# Drl_NEW.net
KiCad netlist of a schematic drawn in EAGLE
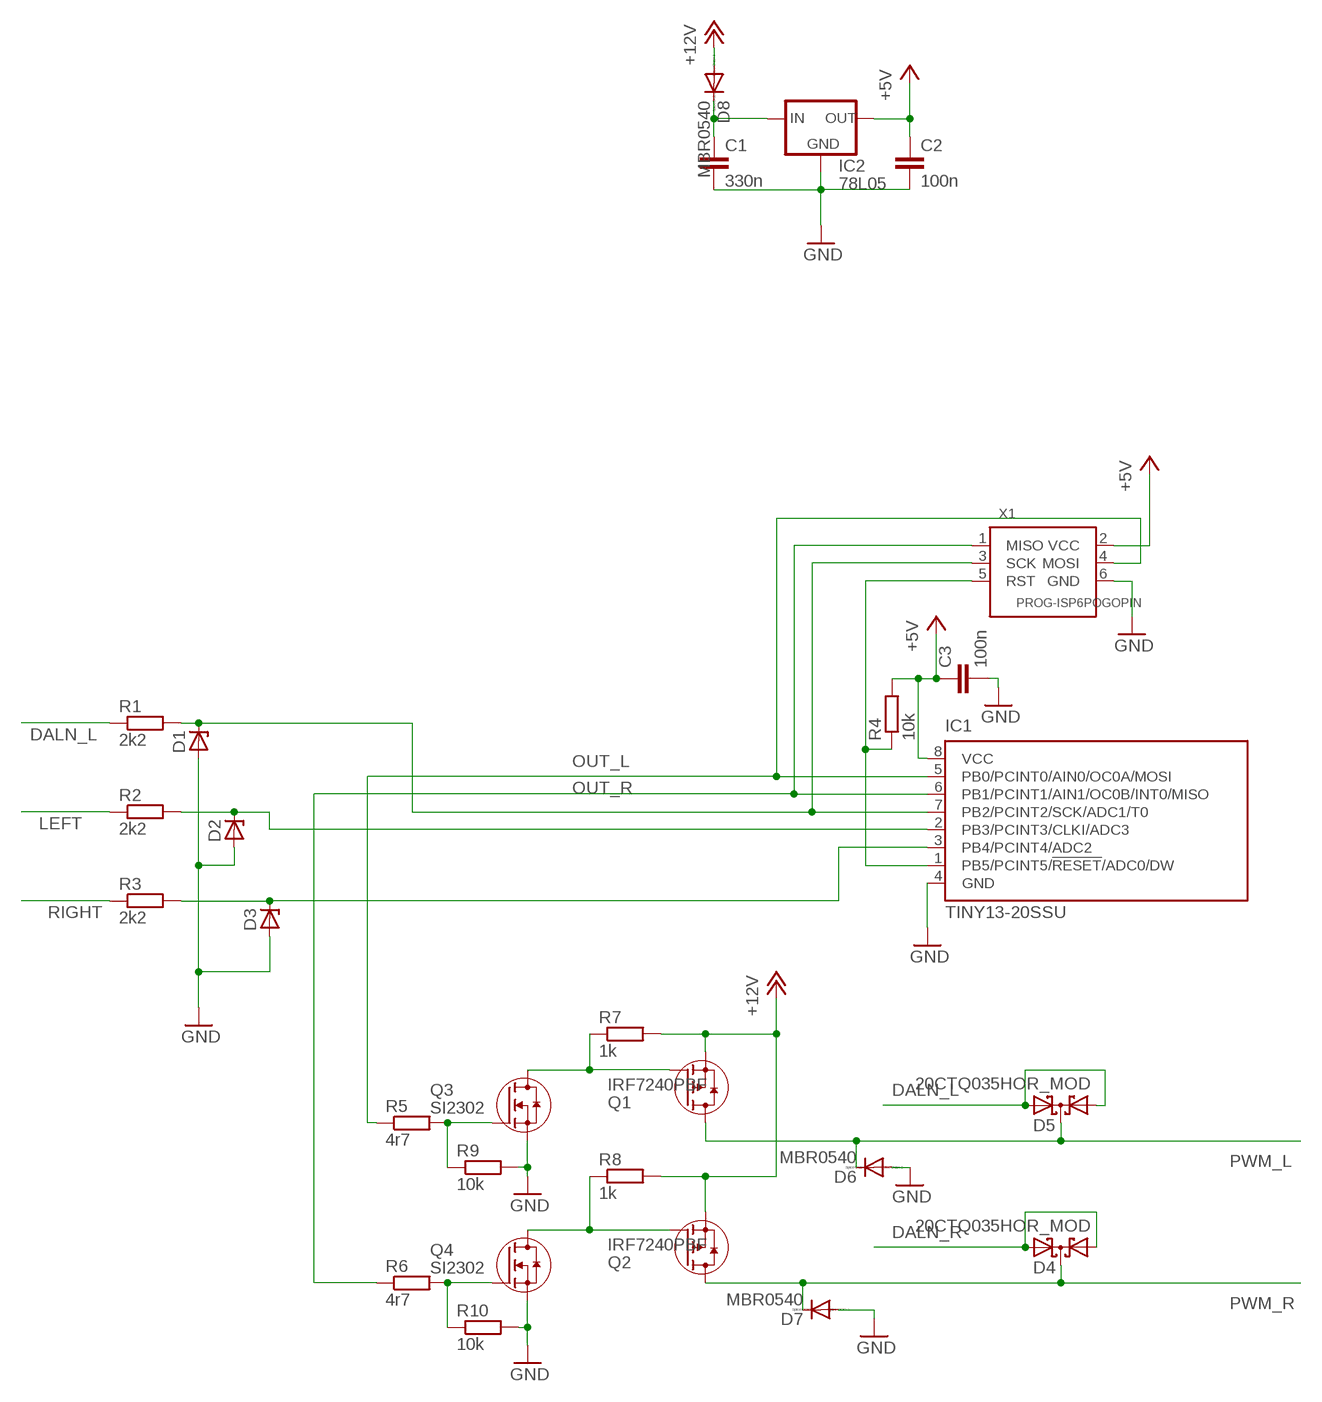
[diagram p0: schematic, sheet 1]

(export (version "E")
  (design (tool "Eeschema 10.0.6"))
  (components
    (comp (ref "C1")
      (value "330n")
      (footprint "eagle-import:C0805")
      (libsource (lib "eagle-import") (part "C-EUC0805"))
    )
    (comp (ref "C2")
      (value "100n")
      (footprint "eagle-import:C0805")
      (libsource (lib "eagle-import") (part "C-EUC0805"))
    )
    (comp (ref "C3")
      (value "100n")
      (footprint "eagle-import:C0805")
      (libsource (lib "eagle-import") (part "C-EUC0805"))
    )
    (comp (ref "D1")
      (value "ZENER-DIODESOD80C")
      (footprint "eagle-import:SOD80C")
      (libsource (lib "eagle-import") (part "ZENER-DIODESOD80C"))
    )
    (comp (ref "D2")
      (value "ZENER-DIODESOD80C")
      (footprint "eagle-import:SOD80C")
      (libsource (lib "eagle-import") (part "ZENER-DIODESOD80C"))
    )
    (comp (ref "D3")
      (value "ZENER-DIODESOD80C")
      (footprint "eagle-import:SOD80C")
      (libsource (lib "eagle-import") (part "ZENER-DIODESOD80C"))
    )
    (comp (ref "D4")
      (value "20CTQ035HOR_MOD")
      (footprint "eagle-import:TO220AB_MOD")
      (libsource (lib "eagle-import") (part "20CTQ035HOR_MOD"))
    )
    (comp (ref "D5")
      (value "20CTQ035HOR_MOD")
      (footprint "eagle-import:TO220AB_MOD")
      (libsource (lib "eagle-import") (part "20CTQ035HOR_MOD"))
    )
    (comp (ref "D6")
      (value "MBR0540")
      (footprint "eagle-import:SOD-123_MINI-SMA")
      (libsource (lib "eagle-import") (part "CGRM400-G1"))
    )
    (comp (ref "D7")
      (value "MBR0540")
      (footprint "eagle-import:SOD-123_MINI-SMA")
      (libsource (lib "eagle-import") (part "CGRM400-G1"))
    )
    (comp (ref "D8")
      (value "MBR0540")
      (footprint "eagle-import:SOD-123_MINI-SMA")
      (libsource (lib "eagle-import") (part "CGRM400-G1"))
    )
    (comp (ref "IC1")
      (value "TINY13-20SSU")
      (footprint "eagle-import:8S1")
      (fields (field (name "MPN") "ATTINY13-20SSU"))
      (libsource (lib "eagle-import") (part "TINY13SSU-20"))
    )
    (comp (ref "IC2")
      (value "78L05")
      (footprint "eagle-import:78LXX-SOT89")
      (libsource (lib "eagle-import") (part "78LXXSOT89"))
    )
    (comp (ref "Q1")
      (value "IRF7240PBF")
      (footprint "eagle-import:SO08")
      (libsource (lib "eagle-import") (part "IRF7240PBF"))
    )
    (comp (ref "Q2")
      (value "IRF7240PBF")
      (footprint "eagle-import:SO08")
      (libsource (lib "eagle-import") (part "IRF7240PBF"))
    )
    (comp (ref "Q3")
      (value "SI2302")
      (footprint "eagle-import:SOT-23-GSD")
      (libsource (lib "eagle-import") (part "SI2302"))
    )
    (comp (ref "Q4")
      (value "SI2302")
      (footprint "eagle-import:SOT-23-GSD")
      (libsource (lib "eagle-import") (part "SI2302"))
    )
    (comp (ref "R1")
      (value "2k2")
      (footprint "eagle-import:R0603")
      (libsource (lib "eagle-import") (part "R-EU_R0603"))
    )
    (comp (ref "R2")
      (value "2k2")
      (footprint "eagle-import:R0603")
      (libsource (lib "eagle-import") (part "R-EU_R0603"))
    )
    (comp (ref "R3")
      (value "2k2")
      (footprint "eagle-import:R0603")
      (libsource (lib "eagle-import") (part "R-EU_R0603"))
    )
    (comp (ref "R4")
      (value "10k")
      (footprint "eagle-import:R0603")
      (libsource (lib "eagle-import") (part "R-EU_R0603"))
    )
    (comp (ref "R5")
      (value "4r7")
      (footprint "eagle-import:R0603")
      (libsource (lib "eagle-import") (part "R-EU_R0603"))
    )
    (comp (ref "R6")
      (value "4r7")
      (footprint "eagle-import:R0603")
      (libsource (lib "eagle-import") (part "R-EU_R0603"))
    )
    (comp (ref "R7")
      (value "1k")
      (footprint "eagle-import:R0603")
      (libsource (lib "eagle-import") (part "R-EU_R0603"))
    )
    (comp (ref "R8")
      (value "1k")
      (footprint "eagle-import:R0603")
      (libsource (lib "eagle-import") (part "R-EU_R0603"))
    )
    (comp (ref "R9")
      (value "10k")
      (footprint "eagle-import:R0603")
      (libsource (lib "eagle-import") (part "R-EU_R0603"))
    )
    (comp (ref "R10")
      (value "10k")
      (footprint "eagle-import:R0603")
      (libsource (lib "eagle-import") (part "R-EU_R0603"))
    )
    (comp (ref "X1")
      (value "PROG-ISP6POGOPIN")
      (footprint "eagle-import:PROG_POGOPIN")
      (libsource (lib "eagle-import") (part "PROG-ISP6POGOPIN"))
    )
  )
  (nets
    (net (code "1") (name "+5V") (class "Default")
      (node (ref "C2") (pin "1") (pinfunction "1_1") (pintype "passive"))
      (node (ref "C3") (pin "1") (pinfunction "1_1") (pintype "passive"))
      (node (ref "IC1") (pin "8") (pinfunction "VCC_8") (pintype "power_in"))
      (node (ref "IC2") (pin "OUT") (pinfunction "OUT_OUT") (pintype "passive"))
      (node (ref "R4") (pin "2") (pinfunction "2_2") (pintype "passive"))
      (node (ref "X1") (pin "2") (pinfunction "VCC_2") (pintype "bidirectional"))
    )
    (net (code "2") (name "+12V") (class "Default")
      (node (ref "D8") (pin "A") (pinfunction "A_A") (pintype "passive"))
      (node (ref "Q1") (pin "1") (pinfunction "S_1") (pintype "passive"))
      (node (ref "Q1") (pin "2") (pinfunction "S_2") (pintype "passive"))
      (node (ref "Q1") (pin "3") (pinfunction "S_3") (pintype "passive"))
      (node (ref "Q2") (pin "1") (pinfunction "S_1") (pintype "passive"))
      (node (ref "Q2") (pin "2") (pinfunction "S_2") (pintype "passive"))
      (node (ref "Q2") (pin "3") (pinfunction "S_3") (pintype "passive"))
      (node (ref "R7") (pin "2") (pinfunction "2_2") (pintype "passive"))
      (node (ref "R8") (pin "2") (pinfunction "2_2") (pintype "passive"))
    )
    (net (code "3") (name "/DALN_L") (class "Default")
      (node (ref "D5") (pin "A1") (pinfunction "A1_A1") (pintype "passive"))
      (node (ref "D5") (pin "A2") (pinfunction "A2_A2") (pintype "passive"))
      (node (ref "R1") (pin "1") (pinfunction "1_1") (pintype "passive"))
    )
    (net (code "4") (name "/DALN_R") (class "Default")
      (node (ref "D4") (pin "A1") (pinfunction "A1_A1") (pintype "passive"))
      (node (ref "D4") (pin "A2") (pinfunction "A2_A2") (pintype "passive"))
    )
    (net (code "5") (name "/LEFT") (class "Default")
      (node (ref "R2") (pin "1") (pinfunction "1_1") (pintype "passive"))
    )
    (net (code "6") (name "/OUT_L") (class "Default")
      (node (ref "IC1") (pin "5") (pinfunction "PB0/PCINT0/AIN0/OC0A/MOSI_5") (pintype "bidirectional"))
      (node (ref "R5") (pin "1") (pinfunction "1_1") (pintype "passive"))
      (node (ref "X1") (pin "4") (pinfunction "MOSI_4") (pintype "bidirectional"))
    )
    (net (code "7") (name "/OUT_R") (class "Default")
      (node (ref "IC1") (pin "6") (pinfunction "PB1/PCINT1/AIN1/OC0B/INT0/MISO_6") (pintype "bidirectional"))
      (node (ref "R6") (pin "1") (pinfunction "1_1") (pintype "passive"))
      (node (ref "X1") (pin "1") (pinfunction "MISO_1") (pintype "bidirectional"))
    )
    (net (code "8") (name "/PWM_L") (class "Default")
      (node (ref "D5") (pin "C") (pinfunction "C_C") (pintype "passive"))
      (node (ref "D6") (pin "C") (pinfunction "C_C") (pintype "passive"))
      (node (ref "Q1") (pin "5") (pinfunction "D_5") (pintype "passive"))
      (node (ref "Q1") (pin "6") (pinfunction "D_6") (pintype "passive"))
      (node (ref "Q1") (pin "7") (pinfunction "D_7") (pintype "passive"))
      (node (ref "Q1") (pin "8") (pinfunction "D_8") (pintype "passive"))
    )
    (net (code "9") (name "/PWM_R") (class "Default")
      (node (ref "D4") (pin "C") (pinfunction "C_C") (pintype "passive"))
      (node (ref "D7") (pin "C") (pinfunction "C_C") (pintype "passive"))
      (node (ref "Q2") (pin "5") (pinfunction "D_5") (pintype "passive"))
      (node (ref "Q2") (pin "6") (pinfunction "D_6") (pintype "passive"))
      (node (ref "Q2") (pin "7") (pinfunction "D_7") (pintype "passive"))
      (node (ref "Q2") (pin "8") (pinfunction "D_8") (pintype "passive"))
    )
    (net (code "10") (name "/RIGHT") (class "Default")
      (node (ref "R3") (pin "1") (pinfunction "1_1") (pintype "passive"))
    )
    (net (code "11") (name "GND") (class "Default")
      (node (ref "C1") (pin "2") (pinfunction "2_2") (pintype "passive"))
      (node (ref "C2") (pin "2") (pinfunction "2_2") (pintype "passive"))
      (node (ref "C3") (pin "2") (pinfunction "2_2") (pintype "passive"))
      (node (ref "D1") (pin "A") (pinfunction "A_A") (pintype "passive"))
      (node (ref "D2") (pin "A") (pinfunction "A_A") (pintype "passive"))
      (node (ref "D3") (pin "A") (pinfunction "A_A") (pintype "passive"))
      (node (ref "D6") (pin "A") (pinfunction "A_A") (pintype "passive"))
      (node (ref "D7") (pin "A") (pinfunction "A_A") (pintype "passive"))
      (node (ref "IC1") (pin "4") (pinfunction "GND_4") (pintype "power_in"))
      (node (ref "IC2") (pin "GND@0") (pinfunction "GND_GND@0") (pintype "input"))
      (node (ref "IC2") (pin "GND@1") (pinfunction "GND_GND@1") (pintype "input"))
      (node (ref "Q3") (pin "S") (pinfunction "S_S") (pintype "passive"))
      (node (ref "Q4") (pin "S") (pinfunction "S_S") (pintype "passive"))
      (node (ref "R10") (pin "2") (pinfunction "2_2") (pintype "passive"))
      (node (ref "R9") (pin "2") (pinfunction "2_2") (pintype "passive"))
      (node (ref "X1") (pin "6") (pinfunction "GND_6") (pintype "power_in"))
    )
    (net (code "12") (name "Net-(C1-Pad1)") (class "Default")
      (node (ref "C1") (pin "1") (pinfunction "1_1") (pintype "passive"))
      (node (ref "D8") (pin "C") (pinfunction "C_C") (pintype "passive"))
      (node (ref "IC2") (pin "IN") (pinfunction "IN_IN") (pintype "input"))
    )
    (net (code "13") (name "Net-(IC1-PB2{slash}PCINT2{slash}SCK{slash}ADC1{slash}T0)") (class "Default")
      (node (ref "D1") (pin "C") (pinfunction "C_C") (pintype "passive"))
      (node (ref "IC1") (pin "7") (pinfunction "PB2/PCINT2/SCK/ADC1/T0_7") (pintype "bidirectional"))
      (node (ref "R1") (pin "2") (pinfunction "2_2") (pintype "passive"))
      (node (ref "X1") (pin "3") (pinfunction "SCK_3") (pintype "bidirectional"))
    )
    (net (code "14") (name "Net-(IC1-PB3{slash}PCINT3{slash}CLKI{slash}ADC3)") (class "Default")
      (node (ref "D2") (pin "C") (pinfunction "C_C") (pintype "passive"))
      (node (ref "IC1") (pin "2") (pinfunction "PB3/PCINT3/CLKI/ADC3_2") (pintype "bidirectional"))
      (node (ref "R2") (pin "2") (pinfunction "2_2") (pintype "passive"))
    )
    (net (code "15") (name "Net-(IC1-PB4{slash}PCINT4{slash}ADC2)") (class "Default")
      (node (ref "D3") (pin "C") (pinfunction "C_C") (pintype "passive"))
      (node (ref "IC1") (pin "3") (pinfunction "PB4/PCINT4/ADC2_3") (pintype "bidirectional"))
      (node (ref "R3") (pin "2") (pinfunction "2_2") (pintype "passive"))
    )
    (net (code "16") (name "Net-(IC1-PB5{slash}PCINT5{slash}~{RESET}{slash}ADC0{slash}DW)") (class "Default")
      (node (ref "IC1") (pin "1") (pinfunction "PB5/PCINT5/~{RESET}/ADC0/DW_1") (pintype "bidirectional"))
      (node (ref "R4") (pin "1") (pinfunction "1_1") (pintype "passive"))
      (node (ref "X1") (pin "5") (pinfunction "RST_5") (pintype "bidirectional"))
    )
    (net (code "17") (name "Net-(Q1-G)") (class "Default")
      (node (ref "Q1") (pin "4") (pinfunction "G_4") (pintype "passive"))
      (node (ref "Q3") (pin "D") (pinfunction "D_D") (pintype "passive"))
      (node (ref "R7") (pin "1") (pinfunction "1_1") (pintype "passive"))
    )
    (net (code "18") (name "Net-(Q2-G)") (class "Default")
      (node (ref "Q2") (pin "4") (pinfunction "G_4") (pintype "passive"))
      (node (ref "Q4") (pin "D") (pinfunction "D_D") (pintype "passive"))
      (node (ref "R8") (pin "1") (pinfunction "1_1") (pintype "passive"))
    )
    (net (code "19") (name "Net-(Q3-PadG)") (class "Default")
      (node (ref "Q3") (pin "G") (pinfunction "G_G") (pintype "passive"))
      (node (ref "R5") (pin "2") (pinfunction "2_2") (pintype "passive"))
      (node (ref "R9") (pin "1") (pinfunction "1_1") (pintype "passive"))
    )
    (net (code "20") (name "Net-(Q4-PadG)") (class "Default")
      (node (ref "Q4") (pin "G") (pinfunction "G_G") (pintype "passive"))
      (node (ref "R10") (pin "1") (pinfunction "1_1") (pintype "passive"))
      (node (ref "R6") (pin "2") (pinfunction "2_2") (pintype "passive"))
    )
  )
)
